# 3DO.net
KiCad netlist of a schematic drawn in EAGLE
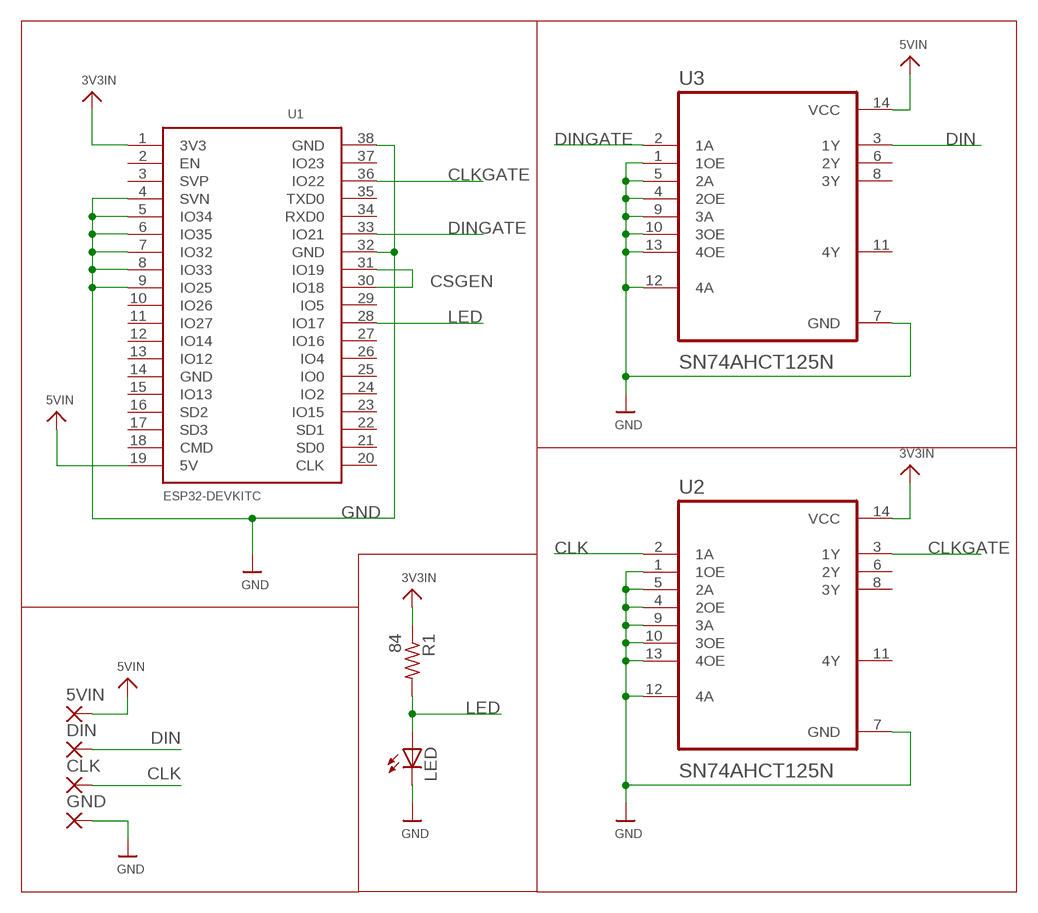
[diagram p0: schematic, sheet 1]

(export (version "E")
  (design (tool "Eeschema 10.0.6"))
  (components
    (comp (ref "5VIN")
      (value "SMD5")
      (footprint "eagle-import:SMD2,54-5,08")
      (libsource (lib "eagle-import") (part "SMD5"))
    )
    (comp (ref "CLK")
      (value "SMD5")
      (footprint "eagle-import:SMD2,54-5,08")
      (libsource (lib "eagle-import") (part "SMD5"))
    )
    (comp (ref "DIN")
      (value "SMD5")
      (footprint "eagle-import:SMD2,54-5,08")
      (libsource (lib "eagle-import") (part "SMD5"))
    )
    (comp (ref "GND")
      (value "SMD5")
      (footprint "eagle-import:SMD2,54-5,08")
      (libsource (lib "eagle-import") (part "SMD5"))
    )
    (comp (ref "LED")
      (value "LEDCHIPLED_1206")
      (footprint "eagle-import:CHIPLED_1206")
      (libsource (lib "eagle-import") (part "LEDCHIPLED_1206"))
    )
    (comp (ref "R1")
      (value "84")
      (footprint "eagle-import:R1206")
      (libsource (lib "eagle-import") (part "R-US_R1206"))
    )
    (comp (ref "U1")
      (value "ESP32DEVKITC")
      (footprint "eagle-import:ESP32-DEVKITC")
      (libsource (lib "eagle-import") (part "ESP32DEVKITC"))
    )
    (comp (ref "U2")
      (value "SN74AHCT125N")
      (footprint "eagle-import:DIP794W45P254L1969H508Q14")
      (fields (field (name "MF") "Texas Instruments"))
      (libsource (lib "eagle-import") (part "SN74AHCT125N"))
    )
    (comp (ref "U3")
      (value "SN74AHCT125N")
      (footprint "eagle-import:DIP794W45P254L1969H508Q14")
      (fields (field (name "MF") "Texas Instruments"))
      (libsource (lib "eagle-import") (part "SN74AHCT125N"))
    )
  )
  (nets
    (net (code "1") (name "/CLK") (class "Default")
      (node (ref "CLK") (pin "1") (pinfunction "P_1") (pintype "passive"))
      (node (ref "U2") (pin "2") (pinfunction "1A_2") (pintype "input"))
    )
    (net (code "2") (name "/CLKGATE") (class "Default")
      (node (ref "U1") (pin "36") (pinfunction "IO22_36") (pintype "bidirectional"))
      (node (ref "U2") (pin "3") (pinfunction "1Y_3") (pintype "output"))
    )
    (net (code "3") (name "/CSGEN") (class "Default")
      (node (ref "U1") (pin "30") (pinfunction "IO18_30") (pintype "bidirectional"))
      (node (ref "U1") (pin "31") (pinfunction "IO19_31") (pintype "bidirectional"))
    )
    (net (code "4") (name "/DIN") (class "Default")
      (node (ref "DIN") (pin "1") (pinfunction "P_1") (pintype "passive"))
      (node (ref "U3") (pin "3") (pinfunction "1Y_3") (pintype "output"))
    )
    (net (code "5") (name "/DINGATE") (class "Default")
      (node (ref "U1") (pin "33") (pinfunction "IO21_33") (pintype "bidirectional"))
      (node (ref "U3") (pin "2") (pinfunction "1A_2") (pintype "input"))
    )
    (net (code "6") (name "/LED") (class "Default")
      (node (ref "LED") (pin "A") (pinfunction "A_A") (pintype "passive"))
      (node (ref "R1") (pin "2") (pinfunction "2_2") (pintype "passive"))
      (node (ref "U1") (pin "28") (pinfunction "IO17_28") (pintype "bidirectional"))
    )
    (net (code "7") (name "3V3IN") (class "Default")
      (node (ref "R1") (pin "1") (pinfunction "1_1") (pintype "passive"))
      (node (ref "U1") (pin "1") (pinfunction "3V3_1") (pintype "bidirectional"))
      (node (ref "U2") (pin "14") (pinfunction "VCC_14") (pintype "power_in"))
    )
    (net (code "8") (name "5VIN") (class "Default")
      (node (ref "5VIN") (pin "1") (pinfunction "P_1") (pintype "passive"))
      (node (ref "U1") (pin "19") (pinfunction "5V_19") (pintype "bidirectional"))
      (node (ref "U3") (pin "14") (pinfunction "VCC_14") (pintype "power_in"))
    )
    (net (code "9") (name "GND") (class "Default")
      (node (ref "GND") (pin "1") (pinfunction "P_1") (pintype "passive"))
      (node (ref "LED") (pin "C") (pinfunction "C_C") (pintype "passive"))
      (node (ref "U1") (pin "32") (pinfunction "GND_32") (pintype "bidirectional"))
      (node (ref "U1") (pin "38") (pinfunction "GND_38") (pintype "bidirectional"))
      (node (ref "U1") (pin "4") (pinfunction "SVN_4") (pintype "bidirectional"))
      (node (ref "U1") (pin "5") (pinfunction "IO34_5") (pintype "bidirectional"))
      (node (ref "U1") (pin "6") (pinfunction "IO35_6") (pintype "bidirectional"))
      (node (ref "U1") (pin "7") (pinfunction "IO32_7") (pintype "bidirectional"))
      (node (ref "U1") (pin "8") (pinfunction "IO33_8") (pintype "bidirectional"))
      (node (ref "U1") (pin "9") (pinfunction "IO25_9") (pintype "bidirectional"))
      (node (ref "U2") (pin "1") (pinfunction "1OE_1") (pintype "input"))
      (node (ref "U2") (pin "10") (pinfunction "3OE_10") (pintype "input"))
      (node (ref "U2") (pin "12") (pinfunction "4A_12") (pintype "bidirectional"))
      (node (ref "U2") (pin "13") (pinfunction "4OE_13") (pintype "input"))
      (node (ref "U2") (pin "4") (pinfunction "2OE_4") (pintype "input"))
      (node (ref "U2") (pin "5") (pinfunction "2A_5") (pintype "input"))
      (node (ref "U2") (pin "7") (pinfunction "GND_7") (pintype "power_in"))
      (node (ref "U2") (pin "9") (pinfunction "3A_9") (pintype "input"))
      (node (ref "U3") (pin "1") (pinfunction "1OE_1") (pintype "input"))
      (node (ref "U3") (pin "10") (pinfunction "3OE_10") (pintype "input"))
      (node (ref "U3") (pin "12") (pinfunction "4A_12") (pintype "bidirectional"))
      (node (ref "U3") (pin "13") (pinfunction "4OE_13") (pintype "input"))
      (node (ref "U3") (pin "4") (pinfunction "2OE_4") (pintype "input"))
      (node (ref "U3") (pin "5") (pinfunction "2A_5") (pintype "input"))
      (node (ref "U3") (pin "7") (pinfunction "GND_7") (pintype "power_in"))
      (node (ref "U3") (pin "9") (pinfunction "3A_9") (pintype "input"))
    )
    (net (code "10") (name "unconnected-(U1-CLK-Pad20)") (class "Default")
      (node (ref "U1") (pin "20") (pinfunction "CLK_20") (pintype "bidirectional"))
    )
    (net (code "11") (name "unconnected-(U1-CMD-Pad18)") (class "Default")
      (node (ref "U1") (pin "18") (pinfunction "CMD_18") (pintype "bidirectional"))
    )
    (net (code "12") (name "unconnected-(U1-EN-Pad2)") (class "Default")
      (node (ref "U1") (pin "2") (pinfunction "EN_2") (pintype "bidirectional"))
    )
    (net (code "13") (name "unconnected-(U1-GND-Pad14)") (class "Default")
      (node (ref "U1") (pin "14") (pinfunction "GND_14") (pintype "bidirectional"))
    )
    (net (code "14") (name "unconnected-(U1-IO0-Pad25)") (class "Default")
      (node (ref "U1") (pin "25") (pinfunction "IO0_25") (pintype "bidirectional"))
    )
    (net (code "15") (name "unconnected-(U1-IO2-Pad24)") (class "Default")
      (node (ref "U1") (pin "24") (pinfunction "IO2_24") (pintype "bidirectional"))
    )
    (net (code "16") (name "unconnected-(U1-IO4-Pad26)") (class "Default")
      (node (ref "U1") (pin "26") (pinfunction "IO4_26") (pintype "bidirectional"))
    )
    (net (code "17") (name "unconnected-(U1-IO5-Pad29)") (class "Default")
      (node (ref "U1") (pin "29") (pinfunction "IO5_29") (pintype "bidirectional"))
    )
    (net (code "18") (name "unconnected-(U1-IO12-Pad13)") (class "Default")
      (node (ref "U1") (pin "13") (pinfunction "IO12_13") (pintype "bidirectional"))
    )
    (net (code "19") (name "unconnected-(U1-IO13-Pad15)") (class "Default")
      (node (ref "U1") (pin "15") (pinfunction "IO13_15") (pintype "bidirectional"))
    )
    (net (code "20") (name "unconnected-(U1-IO14-Pad12)") (class "Default")
      (node (ref "U1") (pin "12") (pinfunction "IO14_12") (pintype "bidirectional"))
    )
    (net (code "21") (name "unconnected-(U1-IO15-Pad23)") (class "Default")
      (node (ref "U1") (pin "23") (pinfunction "IO15_23") (pintype "bidirectional"))
    )
    (net (code "22") (name "unconnected-(U1-IO16-Pad27)") (class "Default")
      (node (ref "U1") (pin "27") (pinfunction "IO16_27") (pintype "bidirectional"))
    )
    (net (code "23") (name "unconnected-(U1-IO23-Pad37)") (class "Default")
      (node (ref "U1") (pin "37") (pinfunction "IO23_37") (pintype "bidirectional"))
    )
    (net (code "24") (name "unconnected-(U1-IO26-Pad10)") (class "Default")
      (node (ref "U1") (pin "10") (pinfunction "IO26_10") (pintype "bidirectional"))
    )
    (net (code "25") (name "unconnected-(U1-IO27-Pad11)") (class "Default")
      (node (ref "U1") (pin "11") (pinfunction "IO27_11") (pintype "bidirectional"))
    )
    (net (code "26") (name "unconnected-(U1-RXD0-Pad34)") (class "Default")
      (node (ref "U1") (pin "34") (pinfunction "RXD0_34") (pintype "bidirectional"))
    )
    (net (code "27") (name "unconnected-(U1-SD0-Pad21)") (class "Default")
      (node (ref "U1") (pin "21") (pinfunction "SD0_21") (pintype "bidirectional"))
    )
    (net (code "28") (name "unconnected-(U1-SD1-Pad22)") (class "Default")
      (node (ref "U1") (pin "22") (pinfunction "SD1_22") (pintype "bidirectional"))
    )
    (net (code "29") (name "unconnected-(U1-SD2-Pad16)") (class "Default")
      (node (ref "U1") (pin "16") (pinfunction "SD2_16") (pintype "bidirectional"))
    )
    (net (code "30") (name "unconnected-(U1-SD3-Pad17)") (class "Default")
      (node (ref "U1") (pin "17") (pinfunction "SD3_17") (pintype "bidirectional"))
    )
    (net (code "31") (name "unconnected-(U1-SVP-Pad3)") (class "Default")
      (node (ref "U1") (pin "3") (pinfunction "SVP_3") (pintype "bidirectional"))
    )
    (net (code "32") (name "unconnected-(U1-TXD0-Pad35)") (class "Default")
      (node (ref "U1") (pin "35") (pinfunction "TXD0_35") (pintype "bidirectional"))
    )
    (net (code "33") (name "unconnected-(U2-2Y-Pad6)") (class "Default")
      (node (ref "U2") (pin "6") (pinfunction "2Y_6") (pintype "output"))
    )
    (net (code "34") (name "unconnected-(U2-3Y-Pad8)") (class "Default")
      (node (ref "U2") (pin "8") (pinfunction "3Y_8") (pintype "output"))
    )
    (net (code "35") (name "unconnected-(U2-4Y-Pad11)") (class "Default")
      (node (ref "U2") (pin "11") (pinfunction "4Y_11") (pintype "output"))
    )
    (net (code "36") (name "unconnected-(U3-2Y-Pad6)") (class "Default")
      (node (ref "U3") (pin "6") (pinfunction "2Y_6") (pintype "output"))
    )
    (net (code "37") (name "unconnected-(U3-3Y-Pad8)") (class "Default")
      (node (ref "U3") (pin "8") (pinfunction "3Y_8") (pintype "output"))
    )
    (net (code "38") (name "unconnected-(U3-4Y-Pad11)") (class "Default")
      (node (ref "U3") (pin "11") (pinfunction "4Y_11") (pintype "output"))
    )
  )
)
